# DNS.net
KiCad netlist of a schematic drawn in EAGLE
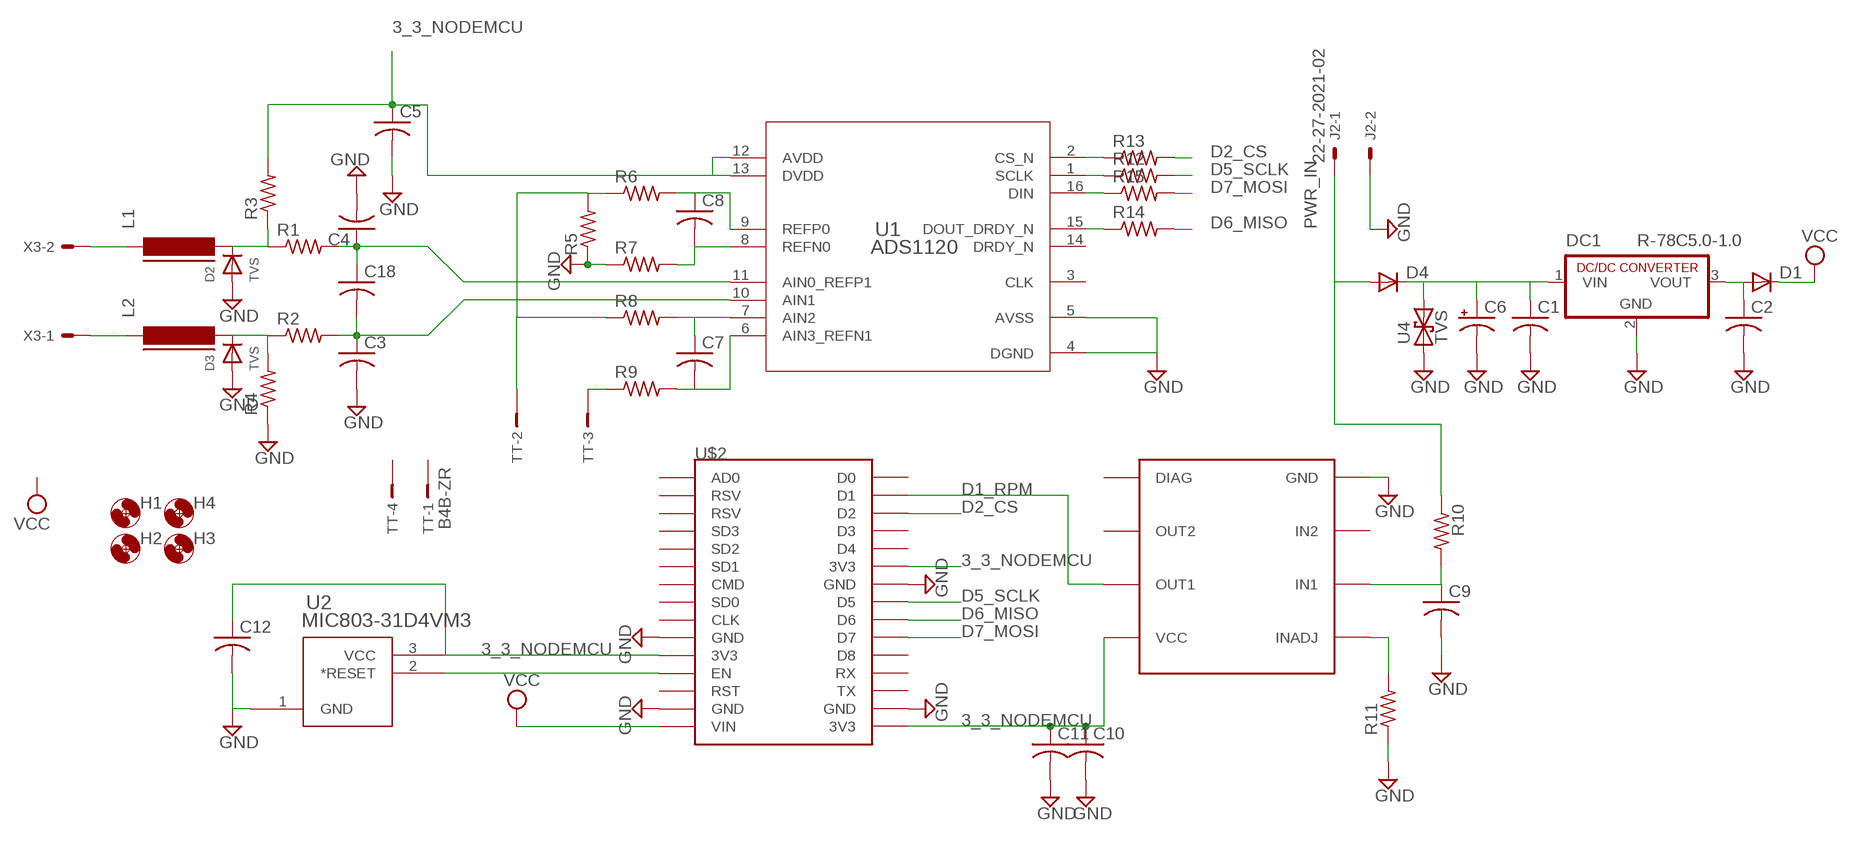
[diagram p0: schematic, sheet 1]

(export (version "E")
  (design (tool "Eeschema 10.0.6"))
  (components
    (comp (ref "C1")
      (value "C-USC0805")
      (footprint "eagle-import:C0805")
      (libsource (lib "eagle-import") (part "C-USC0805"))
    )
    (comp (ref "C2")
      (value "C-USC0805")
      (footprint "eagle-import:C0805")
      (libsource (lib "eagle-import") (part "C-USC0805"))
    )
    (comp (ref "C3")
      (value "C-USC0805")
      (footprint "eagle-import:C0805")
      (libsource (lib "eagle-import") (part "C-USC0805"))
    )
    (comp (ref "C4")
      (value "C-USC0805")
      (footprint "eagle-import:C0805")
      (libsource (lib "eagle-import") (part "C-USC0805"))
    )
    (comp (ref "C5")
      (value "C-USC0805")
      (footprint "eagle-import:C0805")
      (libsource (lib "eagle-import") (part "C-USC0805"))
    )
    (comp (ref "C6")
      (value "CPOL-USE5-10.5")
      (footprint "eagle-import:E5-10,5")
      (libsource (lib "eagle-import") (part "CPOL-USE5-10.5"))
    )
    (comp (ref "C7")
      (value "C-USC0805")
      (footprint "eagle-import:C0805")
      (libsource (lib "eagle-import") (part "C-USC0805"))
    )
    (comp (ref "C8")
      (value "C-USC0805")
      (footprint "eagle-import:C0805")
      (libsource (lib "eagle-import") (part "C-USC0805"))
    )
    (comp (ref "C9")
      (value "C-USC0805")
      (footprint "eagle-import:C0805")
      (libsource (lib "eagle-import") (part "C-USC0805"))
    )
    (comp (ref "C10")
      (value "C-USC0805")
      (footprint "eagle-import:C0805")
      (libsource (lib "eagle-import") (part "C-USC0805"))
    )
    (comp (ref "C11")
      (value "C-USC0805")
      (footprint "eagle-import:C0805")
      (libsource (lib "eagle-import") (part "C-USC0805"))
    )
    (comp (ref "C12")
      (value "C-USC0805")
      (footprint "eagle-import:C0805")
      (libsource (lib "eagle-import") (part "C-USC0805"))
    )
    (comp (ref "C18")
      (value "C-USC0805")
      (footprint "eagle-import:C0805")
      (libsource (lib "eagle-import") (part "C-USC0805"))
    )
    (comp (ref "D1")
      (value "DIODE-DO-214AC")
      (footprint "eagle-import:DO-214AC")
      (libsource (lib "eagle-import") (part "DIODE-DO-214AC"))
    )
    (comp (ref "D2")
      (value "TVS")
      (footprint "eagle-import:SOD-323F")
      (libsource (lib "eagle-import") (part "DIODESOD-323F"))
    )
    (comp (ref "D3")
      (value "TVS")
      (footprint "eagle-import:SOD-323F")
      (libsource (lib "eagle-import") (part "DIODESOD-323F"))
    )
    (comp (ref "D4")
      (value "DIODE-DO-214AC")
      (footprint "eagle-import:DO-214AC")
      (libsource (lib "eagle-import") (part "DIODE-DO-214AC"))
    )
    (comp (ref "DC1")
      (value "R-78C5.0-1.0")
      (footprint "eagle-import:SIP3")
      (libsource (lib "eagle-import") (part "R-78C-1.05.0"))
    )
    (comp (ref "H1")
      (value "MOUNT-HOLE2.8")
      (footprint "eagle-import:2,8")
      (libsource (lib "eagle-import") (part "MOUNT-HOLE2.8"))
    )
    (comp (ref "H2")
      (value "MOUNT-HOLE2.8")
      (footprint "eagle-import:2,8")
      (libsource (lib "eagle-import") (part "MOUNT-HOLE2.8"))
    )
    (comp (ref "H3")
      (value "MOUNT-HOLE2.8")
      (footprint "eagle-import:2,8")
      (libsource (lib "eagle-import") (part "MOUNT-HOLE2.8"))
    )
    (comp (ref "H4")
      (value "MOUNT-HOLE2.8")
      (footprint "eagle-import:2,8")
      (libsource (lib "eagle-import") (part "MOUNT-HOLE2.8"))
    )
    (comp (ref "J2")
      (value "22-27-2021-02")
      (footprint "eagle-import:6410-02")
      (libsource (lib "eagle-import") (part "22-?-0227-2021"))
    )
    (comp (ref "L1")
      (value "FERRITE-0805")
      (footprint "eagle-import:FB805")
      (libsource (lib "eagle-import") (part "FERRITE-0805"))
    )
    (comp (ref "L2")
      (value "FERRITE-0805")
      (footprint "eagle-import:FB805")
      (libsource (lib "eagle-import") (part "FERRITE-0805"))
    )
    (comp (ref "R1")
      (value "R-US_R0805W")
      (footprint "eagle-import:R0805W")
      (libsource (lib "eagle-import") (part "R-US_R0805W"))
    )
    (comp (ref "R2")
      (value "R-US_R0805W")
      (footprint "eagle-import:R0805W")
      (libsource (lib "eagle-import") (part "R-US_R0805W"))
    )
    (comp (ref "R3")
      (value "R-US_R0805W")
      (footprint "eagle-import:R0805W")
      (libsource (lib "eagle-import") (part "R-US_R0805W"))
    )
    (comp (ref "R4")
      (value "R-US_R0805W")
      (footprint "eagle-import:R0805W")
      (libsource (lib "eagle-import") (part "R-US_R0805W"))
    )
    (comp (ref "R5")
      (value "R-US_R0805W")
      (footprint "eagle-import:R0805W")
      (libsource (lib "eagle-import") (part "R-US_R0805W"))
    )
    (comp (ref "R6")
      (value "R-US_R0805W")
      (footprint "eagle-import:R0805W")
      (libsource (lib "eagle-import") (part "R-US_R0805W"))
    )
    (comp (ref "R7")
      (value "R-US_R0805W")
      (footprint "eagle-import:R0805W")
      (libsource (lib "eagle-import") (part "R-US_R0805W"))
    )
    (comp (ref "R8")
      (value "R-US_R0805W")
      (footprint "eagle-import:R0805W")
      (libsource (lib "eagle-import") (part "R-US_R0805W"))
    )
    (comp (ref "R9")
      (value "R-US_R0805W")
      (footprint "eagle-import:R0805W")
      (libsource (lib "eagle-import") (part "R-US_R0805W"))
    )
    (comp (ref "R10")
      (value "R-US_R0805W")
      (footprint "eagle-import:R0805W")
      (libsource (lib "eagle-import") (part "R-US_R0805W"))
    )
    (comp (ref "R11")
      (value "R-US_R0805W")
      (footprint "eagle-import:R0805W")
      (libsource (lib "eagle-import") (part "R-US_R0805W"))
    )
    (comp (ref "R12")
      (value "R-US_R0805W")
      (footprint "eagle-import:R0805W")
      (libsource (lib "eagle-import") (part "R-US_R0805W"))
    )
    (comp (ref "R13")
      (value "R-US_R0805W")
      (footprint "eagle-import:R0805W")
      (libsource (lib "eagle-import") (part "R-US_R0805W"))
    )
    (comp (ref "R14")
      (value "R-US_R0805W")
      (footprint "eagle-import:R0805W")
      (libsource (lib "eagle-import") (part "R-US_R0805W"))
    )
    (comp (ref "R15")
      (value "R-US_R0805W")
      (footprint "eagle-import:R0805W")
      (libsource (lib "eagle-import") (part "R-US_R0805W"))
    )
    (comp (ref "TT")
      (value "B4B-ZR")
      (footprint "eagle-import:B4B-ZR")
      (fields (field (name "MF") "FARNELL") (field (name "MPN") "B4B-ZR(LF)(SN)"))
      (libsource (lib "eagle-import") (part "?4B-ZRB"))
    )
    (comp (ref "U$1")
      (value "NCV1124")
      (footprint "eagle-import:TESTER")
      (libsource (lib "eagle-import") (part "NCV1124"))
    )
    (comp (ref "U$2")
      (value "ESP12E_DEVKIT")
      (footprint "eagle-import:ESP12E_DEVKIT")
      (libsource (lib "eagle-import") (part "ESP12E_DEVKIT"))
    )
    (comp (ref "U1")
      (value "ADS1120")
      (footprint "eagle-import:PW0016A_N")
      (fields
        (field (name "ALTERNATEPARTNUMBER") "ADS1120IPW")
        (field (name "MANUFACTURER") "Texas Instruments")
        (field (name "PARTNUMBER") "ADS1120IPWR")
      )
      (libsource (lib "eagle-import") (part "ADS1120IPWR"))
    )
    (comp (ref "U2")
      (value "MIC803-31D4VM3")
      (footprint "eagle-import:SOT-23_M3")
      (fields
        (field (name "MANUFACTURER_PART_NUMBER") "mic803-31d4vm3")
        (field (name "COPYRIGHT") "Copyright (C) 2015 Accelerated Designs. All rights reserved")
      )
      (libsource (lib "eagle-import") (part "MIC803-31D4VM3"))
    )
    (comp (ref "U4")
      (value "TVS")
      (footprint "eagle-import:SMA-DIODE")
      (libsource (lib "eagle-import") (part "TVS"))
    )
    (comp (ref "X3")
      (value "22-23-2021")
      (footprint "eagle-import:22-23-2021")
      (fields
        (field (name "MF") "MOLEX")
        (field (name "MF_1") "MOLEX")
        (field (name "MPN") "22-23-2021")
        (field (name "OC_FARNELL") "1462926")
        (field (name "OC_NEWARK") "25C3832")
      )
      (libsource (lib "eagle-import") (part "22-23-2021"))
    )
  )
  (nets
    (net (code "1") (name "/3_3_NODEMCU") (class "Default")
      (node (ref "C10") (pin "1") (pinfunction "1_1") (pintype "passive"))
      (node (ref "C11") (pin "1") (pinfunction "1_1") (pintype "passive"))
      (node (ref "C12") (pin "1") (pinfunction "1_1") (pintype "passive"))
      (node (ref "C5") (pin "1") (pinfunction "1_1") (pintype "passive"))
      (node (ref "R3") (pin "2") (pinfunction "2_2") (pintype "passive"))
      (node (ref "U$1") (pin "VCC") (pinfunction "VCC_VCC") (pintype "bidirectional"))
      (node (ref "U$2") (pin "3V3@0") (pinfunction "3V3_3V3@0") (pintype "bidirectional"))
      (node (ref "U$2") (pin "3V3@1") (pinfunction "3V3_3V3@1") (pintype "bidirectional"))
      (node (ref "U$2") (pin "3V3@2") (pinfunction "3V3_3V3@2") (pintype "bidirectional"))
      (node (ref "U1") (pin "12") (pinfunction "AVDD_12") (pintype "power_in"))
      (node (ref "U1") (pin "13") (pinfunction "DVDD_13") (pintype "power_in"))
      (node (ref "U2") (pin "3") (pinfunction "VCC_3") (pintype "power_in"))
    )
    (net (code "2") (name "/D1_RPM") (class "Default")
      (node (ref "U$1") (pin "OUT1") (pinfunction "OUT1_OUT1") (pintype "bidirectional"))
      (node (ref "U$2") (pin "D1") (pinfunction "D1_D1") (pintype "bidirectional"))
    )
    (net (code "3") (name "/D2_CS") (class "Default")
      (node (ref "R13") (pin "2") (pinfunction "2_2") (pintype "passive"))
      (node (ref "U$2") (pin "D2") (pinfunction "D2_D2") (pintype "bidirectional"))
    )
    (net (code "4") (name "/D5_SCLK") (class "Default")
      (node (ref "R12") (pin "2") (pinfunction "2_2") (pintype "passive"))
      (node (ref "U$2") (pin "D5") (pinfunction "D5_D5") (pintype "bidirectional"))
    )
    (net (code "5") (name "/D6_MISO") (class "Default")
      (node (ref "R14") (pin "2") (pinfunction "2_2") (pintype "passive"))
      (node (ref "U$2") (pin "D6") (pinfunction "D6_D6") (pintype "bidirectional"))
    )
    (net (code "6") (name "/D7_MOSI") (class "Default")
      (node (ref "R15") (pin "2") (pinfunction "2_2") (pintype "passive"))
      (node (ref "U$2") (pin "D7") (pinfunction "D7_D7") (pintype "bidirectional"))
    )
    (net (code "7") (name "/PWR_IN") (class "Default")
      (node (ref "D4") (pin "A") (pinfunction "A_A") (pintype "passive"))
      (node (ref "J2") (pin "1") (pinfunction "S_1") (pintype "passive"))
      (node (ref "R10") (pin "1") (pinfunction "1_1") (pintype "passive"))
    )
    (net (code "8") (name "GND") (class "Default")
      (node (ref "C1") (pin "2") (pinfunction "2_2") (pintype "passive"))
      (node (ref "C10") (pin "2") (pinfunction "2_2") (pintype "passive"))
      (node (ref "C11") (pin "2") (pinfunction "2_2") (pintype "passive"))
      (node (ref "C12") (pin "2") (pinfunction "2_2") (pintype "passive"))
      (node (ref "C2") (pin "2") (pinfunction "2_2") (pintype "passive"))
      (node (ref "C3") (pin "2") (pinfunction "2_2") (pintype "passive"))
      (node (ref "C4") (pin "2") (pinfunction "2_2") (pintype "passive"))
      (node (ref "C5") (pin "2") (pinfunction "2_2") (pintype "passive"))
      (node (ref "C6") (pin "-") (pinfunction "-_-") (pintype "passive"))
      (node (ref "C9") (pin "2") (pinfunction "2_2") (pintype "passive"))
      (node (ref "D2") (pin "A") (pinfunction "A_A") (pintype "passive"))
      (node (ref "D3") (pin "A") (pinfunction "A_A") (pintype "passive"))
      (node (ref "DC1") (pin "2") (pinfunction "GND_2") (pintype "passive"))
      (node (ref "J2") (pin "2") (pinfunction "S_2") (pintype "passive"))
      (node (ref "R11") (pin "1") (pinfunction "1_1") (pintype "passive"))
      (node (ref "R4") (pin "1") (pinfunction "1_1") (pintype "passive"))
      (node (ref "R5") (pin "1") (pinfunction "1_1") (pintype "passive"))
      (node (ref "R7") (pin "1") (pinfunction "1_1") (pintype "passive"))
      (node (ref "U$1") (pin "GND") (pinfunction "GND_GND") (pintype "bidirectional"))
      (node (ref "U$2") (pin "GND@0") (pinfunction "GND_GND@0") (pintype "bidirectional"))
      (node (ref "U$2") (pin "GND@1") (pinfunction "GND_GND@1") (pintype "bidirectional"))
      (node (ref "U$2") (pin "GND@2") (pinfunction "GND_GND@2") (pintype "bidirectional"))
      (node (ref "U$2") (pin "GND@3") (pinfunction "GND_GND@3") (pintype "bidirectional"))
      (node (ref "U1") (pin "4") (pinfunction "DGND_4") (pintype "power_in"))
      (node (ref "U1") (pin "5") (pinfunction "AVSS_5") (pintype "power_in"))
      (node (ref "U2") (pin "1") (pinfunction "GND_1") (pintype "power_in"))
      (node (ref "U4") (pin "A") (pinfunction "1_A") (pintype "passive"))
    )
    (net (code "9") (name "Net-(C9-Pad1)") (class "Default")
      (node (ref "C9") (pin "1") (pinfunction "1_1") (pintype "passive"))
      (node (ref "R10") (pin "2") (pinfunction "2_2") (pintype "passive"))
      (node (ref "U$1") (pin "IN1") (pinfunction "IN1_IN1") (pintype "bidirectional"))
    )
    (net (code "10") (name "Net-(D2-PadC)") (class "Default")
      (node (ref "D2") (pin "C") (pinfunction "C_C") (pintype "passive"))
      (node (ref "L1") (pin "2") (pinfunction "2_2") (pintype "passive"))
      (node (ref "R1") (pin "1") (pinfunction "1_1") (pintype "passive"))
      (node (ref "R3") (pin "1") (pinfunction "1_1") (pintype "passive"))
    )
    (net (code "11") (name "Net-(D3-PadC)") (class "Default")
      (node (ref "D3") (pin "C") (pinfunction "C_C") (pintype "passive"))
      (node (ref "L2") (pin "2") (pinfunction "2_2") (pintype "passive"))
      (node (ref "R2") (pin "1") (pinfunction "1_1") (pintype "passive"))
      (node (ref "R4") (pin "2") (pinfunction "2_2") (pintype "passive"))
    )
    (net (code "12") (name "Net-(DC1-VIN)") (class "Default")
      (node (ref "C1") (pin "1") (pinfunction "1_1") (pintype "passive"))
      (node (ref "C6") (pin "+") (pinfunction "+_+") (pintype "passive"))
      (node (ref "D4") (pin "C") (pinfunction "C_C") (pintype "passive"))
      (node (ref "DC1") (pin "1") (pinfunction "VIN_1") (pintype "passive"))
      (node (ref "U4") (pin "C") (pinfunction "2_C") (pintype "passive"))
    )
    (net (code "13") (name "Net-(DC1-VOUT)") (class "Default")
      (node (ref "C2") (pin "1") (pinfunction "1_1") (pintype "passive"))
      (node (ref "D1") (pin "A") (pinfunction "A_A") (pintype "passive"))
      (node (ref "DC1") (pin "3") (pinfunction "VOUT_3") (pintype "passive"))
    )
    (net (code "14") (name "Net-(R11-Pad2)") (class "Default")
      (node (ref "R11") (pin "2") (pinfunction "2_2") (pintype "passive"))
      (node (ref "U$1") (pin "INADJ") (pinfunction "INADJ_INADJ") (pintype "bidirectional"))
    )
    (net (code "15") (name "Net-(TTB-1)") (class "Default")
      (node (ref "R5") (pin "2") (pinfunction "2_2") (pintype "passive"))
      (node (ref "R6") (pin "1") (pinfunction "1_1") (pintype "passive"))
      (node (ref "R8") (pin "1") (pinfunction "1_1") (pintype "passive"))
      (node (ref "TT") (pin "2") (pinfunction "1_2") (pintype "passive"))
    )
    (net (code "16") (name "Net-(TTC-1)") (class "Default")
      (node (ref "R9") (pin "1") (pinfunction "1_1") (pintype "passive"))
      (node (ref "TT") (pin "3") (pinfunction "1_3") (pintype "passive"))
    )
    (net (code "17") (name "Net-(U1-AIN0_REFP1)") (class "Default")
      (node (ref "C18") (pin "1") (pinfunction "1_1") (pintype "passive"))
      (node (ref "C4") (pin "1") (pinfunction "1_1") (pintype "passive"))
      (node (ref "R1") (pin "2") (pinfunction "2_2") (pintype "passive"))
      (node (ref "U1") (pin "11") (pinfunction "AIN0_REFP1_11") (pintype "input"))
    )
    (net (code "18") (name "Net-(U1-AIN1)") (class "Default")
      (node (ref "C18") (pin "2") (pinfunction "2_2") (pintype "passive"))
      (node (ref "C3") (pin "1") (pinfunction "1_1") (pintype "passive"))
      (node (ref "R2") (pin "2") (pinfunction "2_2") (pintype "passive"))
      (node (ref "U1") (pin "10") (pinfunction "AIN1_10") (pintype "input"))
    )
    (net (code "19") (name "Net-(U1-AIN2)") (class "Default")
      (node (ref "C7") (pin "1") (pinfunction "1_1") (pintype "passive"))
      (node (ref "R8") (pin "2") (pinfunction "2_2") (pintype "passive"))
      (node (ref "U1") (pin "7") (pinfunction "AIN2_7") (pintype "input"))
    )
    (net (code "20") (name "Net-(U1-AIN3_REFN1)") (class "Default")
      (node (ref "C7") (pin "2") (pinfunction "2_2") (pintype "passive"))
      (node (ref "R9") (pin "2") (pinfunction "2_2") (pintype "passive"))
      (node (ref "U1") (pin "6") (pinfunction "AIN3_REFN1_6") (pintype "input"))
    )
    (net (code "21") (name "Net-(U1-CS_N)") (class "Default")
      (node (ref "R13") (pin "1") (pinfunction "1_1") (pintype "passive"))
      (node (ref "U1") (pin "2") (pinfunction "CS_N_2") (pintype "input"))
    )
    (net (code "22") (name "Net-(U1-DIN)") (class "Default")
      (node (ref "R15") (pin "1") (pinfunction "1_1") (pintype "passive"))
      (node (ref "U1") (pin "16") (pinfunction "DIN_16") (pintype "input"))
    )
    (net (code "23") (name "Net-(U1-DOUT_DRDY_N)") (class "Default")
      (node (ref "R14") (pin "1") (pinfunction "1_1") (pintype "passive"))
      (node (ref "U1") (pin "15") (pinfunction "DOUT_DRDY_N_15") (pintype "output"))
    )
    (net (code "24") (name "Net-(U1-REFN0)") (class "Default")
      (node (ref "C8") (pin "2") (pinfunction "2_2") (pintype "passive"))
      (node (ref "R7") (pin "2") (pinfunction "2_2") (pintype "passive"))
      (node (ref "U1") (pin "8") (pinfunction "REFN0_8") (pintype "input"))
    )
    (net (code "25") (name "Net-(U1-REFP0)") (class "Default")
      (node (ref "C8") (pin "1") (pinfunction "1_1") (pintype "passive"))
      (node (ref "R6") (pin "2") (pinfunction "2_2") (pintype "passive"))
      (node (ref "U1") (pin "9") (pinfunction "REFP0_9") (pintype "input"))
    )
    (net (code "26") (name "Net-(U1-SCLK)") (class "Default")
      (node (ref "R12") (pin "1") (pinfunction "1_1") (pintype "passive"))
      (node (ref "U1") (pin "1") (pinfunction "SCLK_1") (pintype "input"))
    )
    (net (code "27") (name "Net-(U2-*RESET)") (class "Default")
      (node (ref "U$2") (pin "EN") (pinfunction "EN_EN") (pintype "bidirectional"))
      (node (ref "U2") (pin "2") (pinfunction "*RESET_2") (pintype "passive"))
    )
    (net (code "28") (name "Net-(X3A-S)") (class "Default")
      (node (ref "L2") (pin "1") (pinfunction "1_1") (pintype "passive"))
      (node (ref "X3") (pin "1") (pinfunction "S_1") (pintype "passive"))
    )
    (net (code "29") (name "Net-(X3B-S)") (class "Default")
      (node (ref "L1") (pin "1") (pinfunction "1_1") (pintype "passive"))
      (node (ref "X3") (pin "2") (pinfunction "S_2") (pintype "passive"))
    )
    (net (code "30") (name "VCC") (class "Default")
      (node (ref "D1") (pin "C") (pinfunction "C_C") (pintype "passive"))
      (node (ref "U$2") (pin "VIN") (pinfunction "VIN_VIN") (pintype "bidirectional"))
    )
    (net (code "31") (name "unconnected-(TT-Pad1)") (class "Default")
      (node (ref "TT") (pin "1") (pinfunction "1_1") (pintype "passive"))
    )
    (net (code "32") (name "unconnected-(TTD-1-Pad4)") (class "Default")
      (node (ref "TT") (pin "4") (pinfunction "1_4") (pintype "passive"))
    )
    (net (code "33") (name "unconnected-(U$1-PadDIAG)") (class "Default")
      (node (ref "U$1") (pin "DIAG") (pinfunction "DIAG_DIAG") (pintype "bidirectional"))
    )
    (net (code "34") (name "unconnected-(U$1-PadIN2)") (class "Default")
      (node (ref "U$1") (pin "IN2") (pinfunction "IN2_IN2") (pintype "bidirectional"))
    )
    (net (code "35") (name "unconnected-(U$1-PadOUT2)") (class "Default")
      (node (ref "U$1") (pin "OUT2") (pinfunction "OUT2_OUT2") (pintype "bidirectional"))
    )
    (net (code "36") (name "unconnected-(U$2-PadAD0)") (class "Default")
      (node (ref "U$2") (pin "AD0") (pinfunction "AD0_AD0") (pintype "bidirectional"))
    )
    (net (code "37") (name "unconnected-(U$2-PadCLK)") (class "Default")
      (node (ref "U$2") (pin "CLK") (pinfunction "CLK_CLK") (pintype "bidirectional"))
    )
    (net (code "38") (name "unconnected-(U$2-PadCMD)") (class "Default")
      (node (ref "U$2") (pin "CMD") (pinfunction "CMD_CMD") (pintype "bidirectional"))
    )
    (net (code "39") (name "unconnected-(U$2-PadD0)") (class "Default")
      (node (ref "U$2") (pin "D0") (pinfunction "D0_D0") (pintype "bidirectional"))
    )
    (net (code "40") (name "unconnected-(U$2-PadD3)") (class "Default")
      (node (ref "U$2") (pin "D3") (pinfunction "D3_D3") (pintype "bidirectional"))
    )
    (net (code "41") (name "unconnected-(U$2-PadD4)") (class "Default")
      (node (ref "U$2") (pin "D4") (pinfunction "D4_D4") (pintype "bidirectional"))
    )
    (net (code "42") (name "unconnected-(U$2-PadD8)") (class "Default")
      (node (ref "U$2") (pin "D8") (pinfunction "D8_D8") (pintype "bidirectional"))
    )
    (net (code "43") (name "unconnected-(U$2-PadRST)") (class "Default")
      (node (ref "U$2") (pin "RST") (pinfunction "RST_RST") (pintype "bidirectional"))
    )
    (net (code "44") (name "unconnected-(U$2-PadRX)") (class "Default")
      (node (ref "U$2") (pin "RX") (pinfunction "RX_RX") (pintype "bidirectional"))
    )
    (net (code "45") (name "unconnected-(U$2-PadSD0)") (class "Default")
      (node (ref "U$2") (pin "SD0") (pinfunction "SD0_SD0") (pintype "bidirectional"))
    )
    (net (code "46") (name "unconnected-(U$2-PadSD1)") (class "Default")
      (node (ref "U$2") (pin "SD1") (pinfunction "SD1_SD1") (pintype "bidirectional"))
    )
    (net (code "47") (name "unconnected-(U$2-PadSD2)") (class "Default")
      (node (ref "U$2") (pin "SD2") (pinfunction "SD2_SD2") (pintype "bidirectional"))
    )
    (net (code "48") (name "unconnected-(U$2-PadSD3)") (class "Default")
      (node (ref "U$2") (pin "SD3") (pinfunction "SD3_SD3") (pintype "bidirectional"))
    )
    (net (code "49") (name "unconnected-(U$2-PadTX)") (class "Default")
      (node (ref "U$2") (pin "TX") (pinfunction "TX_TX") (pintype "bidirectional"))
    )
    (net (code "50") (name "unconnected-(U$2-RSV-PadRSV@0)") (class "Default")
      (node (ref "U$2") (pin "RSV@0") (pinfunction "RSV_RSV@0") (pintype "bidirectional"))
    )
    (net (code "51") (name "unconnected-(U$2-RSV-PadRSV@1)") (class "Default")
      (node (ref "U$2") (pin "RSV@1") (pinfunction "RSV_RSV@1") (pintype "bidirectional"))
    )
    (net (code "52") (name "unconnected-(U1-CLK-Pad3)") (class "Default")
      (node (ref "U1") (pin "3") (pinfunction "CLK_3") (pintype "input"))
    )
    (net (code "53") (name "unconnected-(U1-DRDY_N-Pad14)") (class "Default")
      (node (ref "U1") (pin "14") (pinfunction "DRDY_N_14") (pintype "output"))
    )
  )
)
